# LED_Chaser.net
KiCad netlist of a schematic drawn in Altium Designer
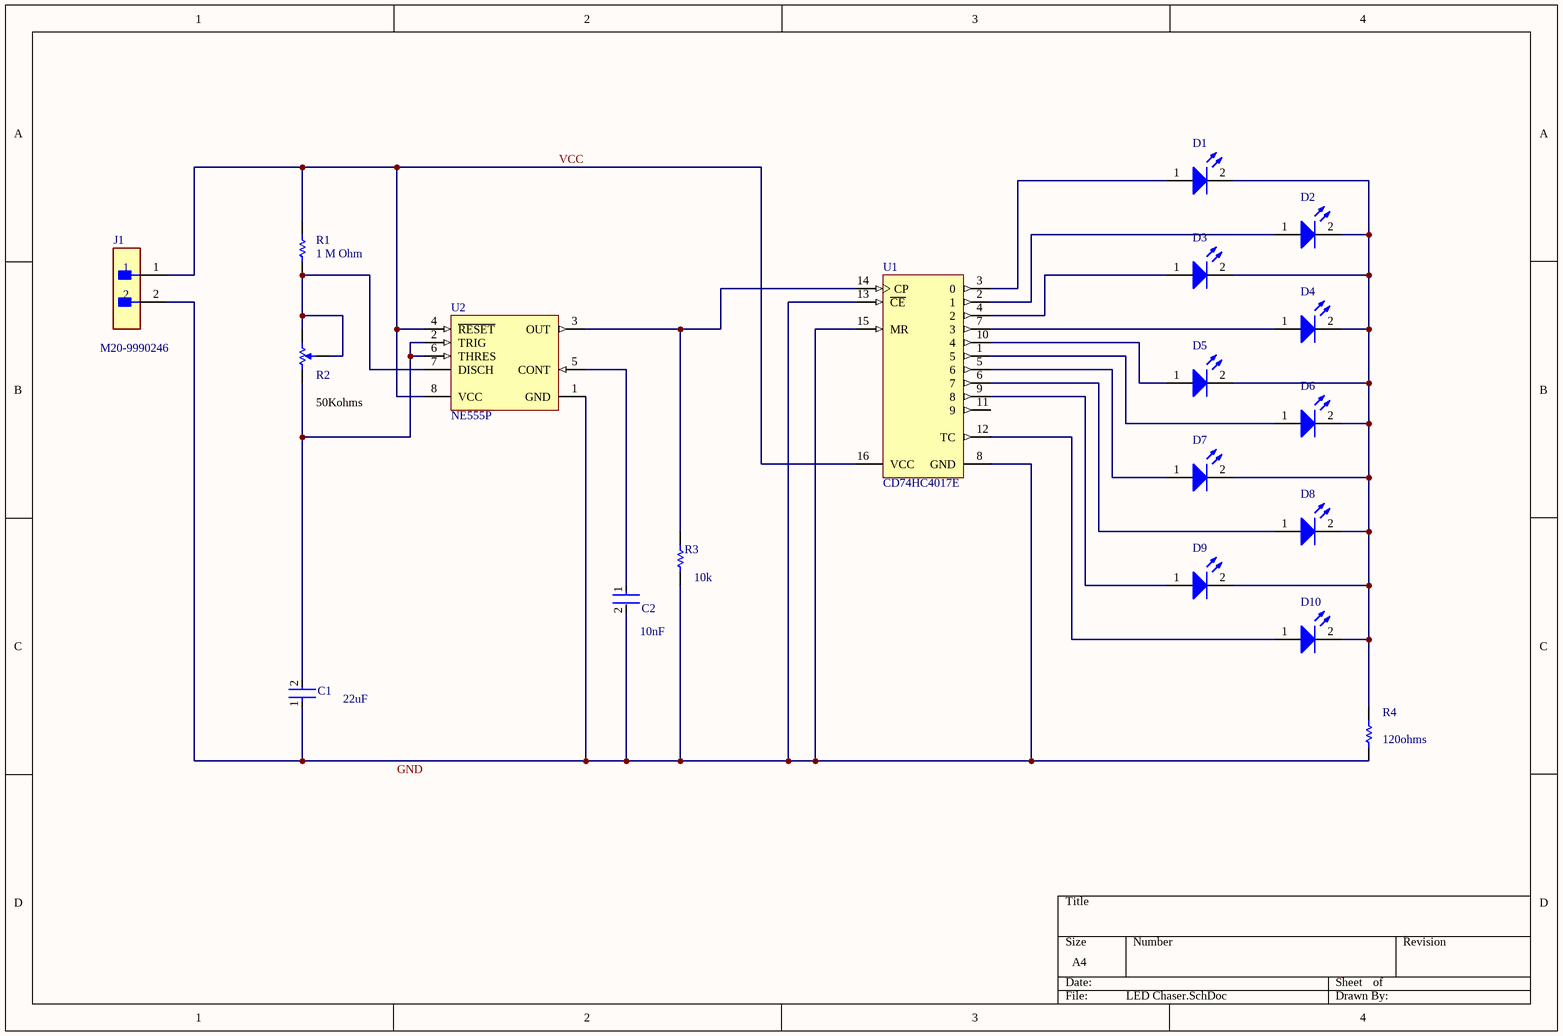
[diagram p0: LED Chaser.SchDoc]

(export (version "E")
  (design (tool "Eeschema 10.0.6"))
  (components
    (comp (ref "C1")
      (value "RCER71E226MWM1H03A")
      (footprint "FP-RCEWM1-MFG")
      (description "CAP CER 22UF 25V X7R RADIAL")
      (fields (field (name "CAPACITANCE") "22uF") (field (name "TOLERANCE") "20%"))
      (libsource (lib "Altium Content Vault") (part "02cd4be3c70576c341d710602a673aa"))
    )
    (comp (ref "C2")
      (value "RCER71H103K0K1H03B")
      (footprint "FP-RCE0K1-MFG")
      (description "Cap Ceramic 10nF 50V X7R ±10% Radial 5mm +125°C Automotive Bulk")
      (fields (field (name "CAPACITANCE") "10nF") (field (name "TOLERANCE") "10%"))
      (libsource (lib "Altium Content Vault") (part "b4654b650e69147ec39a6b967a45e02"))
    )
    (comp (ref "D1")
      (value "151051BS04000")
      (footprint "WL-TMRC_D5.9H8.7")
      (libsource (lib "Altium Content Vault") (part "LED_Blue_1A-2K"))
    )
    (comp (ref "D2")
      (value "151051BS04000")
      (footprint "WL-TMRC_D5.9H8.7")
      (libsource (lib "Altium Content Vault") (part "LED_Blue_1A-2K"))
    )
    (comp (ref "D3")
      (value "151051BS04000")
      (footprint "WL-TMRC_D5.9H8.7")
      (libsource (lib "Altium Content Vault") (part "LED_Blue_1A-2K"))
    )
    (comp (ref "D4")
      (value "151051BS04000")
      (footprint "WL-TMRC_D5.9H8.7")
      (libsource (lib "Altium Content Vault") (part "LED_Blue_1A-2K"))
    )
    (comp (ref "D5")
      (value "151051BS04000")
      (footprint "WL-TMRC_D5.9H8.7")
      (libsource (lib "Altium Content Vault") (part "LED_Blue_1A-2K"))
    )
    (comp (ref "D6")
      (value "151051BS04000")
      (footprint "WL-TMRC_D5.9H8.7")
      (libsource (lib "Altium Content Vault") (part "LED_Blue_1A-2K"))
    )
    (comp (ref "D7")
      (value "151051BS04000")
      (footprint "WL-TMRC_D5.9H8.7")
      (libsource (lib "Altium Content Vault") (part "LED_Blue_1A-2K"))
    )
    (comp (ref "D8")
      (value "151051BS04000")
      (footprint "WL-TMRC_D5.9H8.7")
      (libsource (lib "Altium Content Vault") (part "LED_Blue_1A-2K"))
    )
    (comp (ref "D9")
      (value "151051BS04000")
      (footprint "WL-TMRC_D5.9H8.7")
      (libsource (lib "Altium Content Vault") (part "LED_Blue_1A-2K"))
    )
    (comp (ref "D10")
      (value "151051BS04000")
      (footprint "WL-TMRC_D5.9H8.7")
      (libsource (lib "Altium Content Vault") (part "LED_Blue_1A-2K"))
    )
    (comp (ref "J1")
      (value "M20-9990246")
      (footprint "FP-M20-9990246-MFG")
      (description "Connector Header Through Hole 2 position 0.100\" (2.54mm)")
      (fields (field (name "OCTOPART") "https://octopart.com/m20-9990246-harwin-2590635"))
      (libsource (lib "Altium Content Vault") (part "3bc925449376181038e59eaffc5286c"))
    )
    (comp (ref "R1")
      (value "MFR-25FBF52-1M")
      (footprint "RESA60-630X240")
      (description "Axial Resistor, 1 MOhm, +/- 1%, 250 mW, -55 to 155 degC, 2-Pin THD, RoHS, Bulk")
      (fields (field (name "RESISTANCE") "1 M Ohm") (field (name "TOLERANCE") "1%"))
      (libsource (lib "Altium Content Vault") (part "RES-2"))
    )
    (comp (ref "R2")
      (value "3313J-1-503E")
      (footprint "BOUR-3313J-1_V")
      (fields (field (name "MANUFACTURER") "Bourns"))
      (libsource (lib "Altium Content Vault") (part "RES-ADJ-3_A"))
    )
    (comp (ref "R3")
      (value "OD103JE")
      (footprint "OMTE-RES7X2.5-2")
      (fields
        (field (name "RESISTANCE (OHMS)") "10k")
        (field (name "TOLERANCE") "±5%")
        (field (name "MANUFACTURER") "Ohmite")
      )
      (libsource (lib "Altium Content Vault") (part "RES-2"))
    )
    (comp (ref "R4")
      (value "OD103JE")
      (footprint "OMTE-RES7X2.5-2")
      (fields
        (field (name "RESISTANCE (OHMS)") "120ohms")
        (field (name "TOLERANCE") "±5%")
        (field (name "MANUFACTURER") "Ohmite")
      )
      (libsource (lib "Altium Content Vault") (part "RES-2"))
    )
    (comp (ref "U1")
      (value "CD74HC4017E")
      (footprint "N0016A")
      (description "High Speed CMOS Logic Decade Counter/Divider with 10 Decoded Outputs, N0016A, TUBE")
      (fields
        (field (name "GENERIC PART NUMBER") "CD74HC4017")
        (field (name "MANUFACTURER") "Texas Instruments")
      )
      (libsource (lib "Altium Content Vault") (part "TI-CD74HC4017-16"))
    )
    (comp (ref "U2")
      (value "NE555P")
      (footprint "P0008A")
      (description "Precision Timer, 4.5 to 16 V, 0 to 70 degC, 8-Pin DIP, Pb-Free, Tube")
      (fields (field (name "MANUFACTURER") "TexasInstruments"))
      (libsource (lib "Altium Content Vault") (part "TI-NE555-P8"))
    )
  )
  (nets
    (net (code "1") (name "/GND") (class "Default")
      (node (ref "C1") (pin "1") (pinfunction "1_1") (pintype "passive"))
      (node (ref "C2") (pin "2") (pinfunction "2_2") (pintype "passive"))
      (node (ref "J1") (pin "2") (pinfunction "2_2") (pintype "passive"))
      (node (ref "R3") (pin "1") (pinfunction "1_1") (pintype "passive"))
      (node (ref "R4") (pin "1") (pinfunction "1_1") (pintype "passive"))
      (node (ref "U1") (pin "13") (pinfunction "~{CE}_13") (pintype "input"))
      (node (ref "U1") (pin "15") (pinfunction "MR_15") (pintype "input"))
      (node (ref "U1") (pin "8") (pinfunction "GND_8") (pintype "power_in"))
      (node (ref "U2") (pin "1") (pinfunction "GND_1") (pintype "power_in"))
    )
    (net (code "2") (name "/VCC") (class "Default")
      (node (ref "J1") (pin "1") (pinfunction "1_1") (pintype "passive"))
      (node (ref "R1") (pin "1") (pinfunction "1_1") (pintype "passive"))
      (node (ref "U1") (pin "16") (pinfunction "VCC_16") (pintype "power_in"))
      (node (ref "U2") (pin "4") (pinfunction "~{RESET}_4") (pintype "input"))
      (node (ref "U2") (pin "8") (pinfunction "VCC_8") (pintype "power_in"))
    )
    (net (code "3") (name "Net-(D1-A)") (class "Default")
      (node (ref "D1") (pin "1") (pinfunction "A_1") (pintype "passive"))
      (node (ref "U1") (pin "3") (pinfunction "0_3") (pintype "output"))
    )
    (net (code "4") (name "Net-(D1-K)") (class "Default")
      (node (ref "D1") (pin "2") (pinfunction "K_2") (pintype "passive"))
      (node (ref "D10") (pin "2") (pinfunction "K_2") (pintype "passive"))
      (node (ref "D2") (pin "2") (pinfunction "K_2") (pintype "passive"))
      (node (ref "D3") (pin "2") (pinfunction "K_2") (pintype "passive"))
      (node (ref "D4") (pin "2") (pinfunction "K_2") (pintype "passive"))
      (node (ref "D5") (pin "2") (pinfunction "K_2") (pintype "passive"))
      (node (ref "D6") (pin "2") (pinfunction "K_2") (pintype "passive"))
      (node (ref "D7") (pin "2") (pinfunction "K_2") (pintype "passive"))
      (node (ref "D8") (pin "2") (pinfunction "K_2") (pintype "passive"))
      (node (ref "D9") (pin "2") (pinfunction "K_2") (pintype "passive"))
      (node (ref "R4") (pin "2") (pinfunction "2_2") (pintype "passive"))
    )
    (net (code "5") (name "Net-(D2-A)") (class "Default")
      (node (ref "D2") (pin "1") (pinfunction "A_1") (pintype "passive"))
      (node (ref "U1") (pin "2") (pinfunction "1_2") (pintype "output"))
    )
    (net (code "6") (name "Net-(D3-A)") (class "Default")
      (node (ref "D3") (pin "1") (pinfunction "A_1") (pintype "passive"))
      (node (ref "U1") (pin "4") (pinfunction "2_4") (pintype "output"))
    )
    (net (code "7") (name "Net-(D4-A)") (class "Default")
      (node (ref "D4") (pin "1") (pinfunction "A_1") (pintype "passive"))
      (node (ref "U1") (pin "7") (pinfunction "3_7") (pintype "output"))
    )
    (net (code "8") (name "Net-(D5-A)") (class "Default")
      (node (ref "D5") (pin "1") (pinfunction "A_1") (pintype "passive"))
      (node (ref "U1") (pin "10") (pinfunction "4_10") (pintype "output"))
    )
    (net (code "9") (name "Net-(D6-A)") (class "Default")
      (node (ref "D6") (pin "1") (pinfunction "A_1") (pintype "passive"))
      (node (ref "U1") (pin "1") (pinfunction "5_1") (pintype "output"))
    )
    (net (code "10") (name "Net-(D7-A)") (class "Default")
      (node (ref "D7") (pin "1") (pinfunction "A_1") (pintype "passive"))
      (node (ref "U1") (pin "5") (pinfunction "6_5") (pintype "output"))
    )
    (net (code "11") (name "Net-(D8-A)") (class "Default")
      (node (ref "D8") (pin "1") (pinfunction "A_1") (pintype "passive"))
      (node (ref "U1") (pin "6") (pinfunction "7_6") (pintype "output"))
    )
    (net (code "12") (name "Net-(D9-A)") (class "Default")
      (node (ref "D9") (pin "1") (pinfunction "A_1") (pintype "passive"))
      (node (ref "U1") (pin "9") (pinfunction "8_9") (pintype "output"))
    )
    (net (code "13") (name "Net-(D10-A)") (class "Default")
      (node (ref "D10") (pin "1") (pinfunction "A_1") (pintype "passive"))
      (node (ref "U1") (pin "12") (pinfunction "TC_12") (pintype "output"))
    )
    (net (code "14") (name "Net-(U1-CP)") (class "Default")
      (node (ref "R3") (pin "2") (pinfunction "2_2") (pintype "passive"))
      (node (ref "U1") (pin "14") (pinfunction "CP_14") (pintype "input"))
      (node (ref "U2") (pin "3") (pinfunction "OUT_3") (pintype "output"))
    )
    (net (code "15") (name "Net-(U2-CONT)") (class "Default")
      (node (ref "C2") (pin "1") (pinfunction "1_1") (pintype "passive"))
      (node (ref "U2") (pin "5") (pinfunction "CONT_5") (pintype "input"))
    )
    (net (code "16") (name "Net-(U2-DISCH)") (class "Default")
      (node (ref "R1") (pin "2") (pinfunction "2_2") (pintype "passive"))
      (node (ref "R2") (pin "2") (pinfunction "2_2") (pintype "passive"))
      (node (ref "R2") (pin "3") (pinfunction "3_3") (pintype "passive"))
      (node (ref "U2") (pin "7") (pinfunction "DISCH_7") (pintype "open_collector"))
    )
    (net (code "17") (name "Net-(U2-THRES)") (class "Default")
      (node (ref "C1") (pin "2") (pinfunction "2_2") (pintype "passive"))
      (node (ref "R2") (pin "1") (pinfunction "1_1") (pintype "passive"))
      (node (ref "U2") (pin "2") (pinfunction "TRIG_2") (pintype "input"))
      (node (ref "U2") (pin "6") (pinfunction "THRES_6") (pintype "input"))
    )
    (net (code "18") (name "unconnected-(U1-9-Pad11)") (class "Default")
      (node (ref "U1") (pin "11") (pinfunction "9_11") (pintype "output"))
    )
  )
)
